# design.net
KiCad netlist of a schematic drawn in Altium Designer
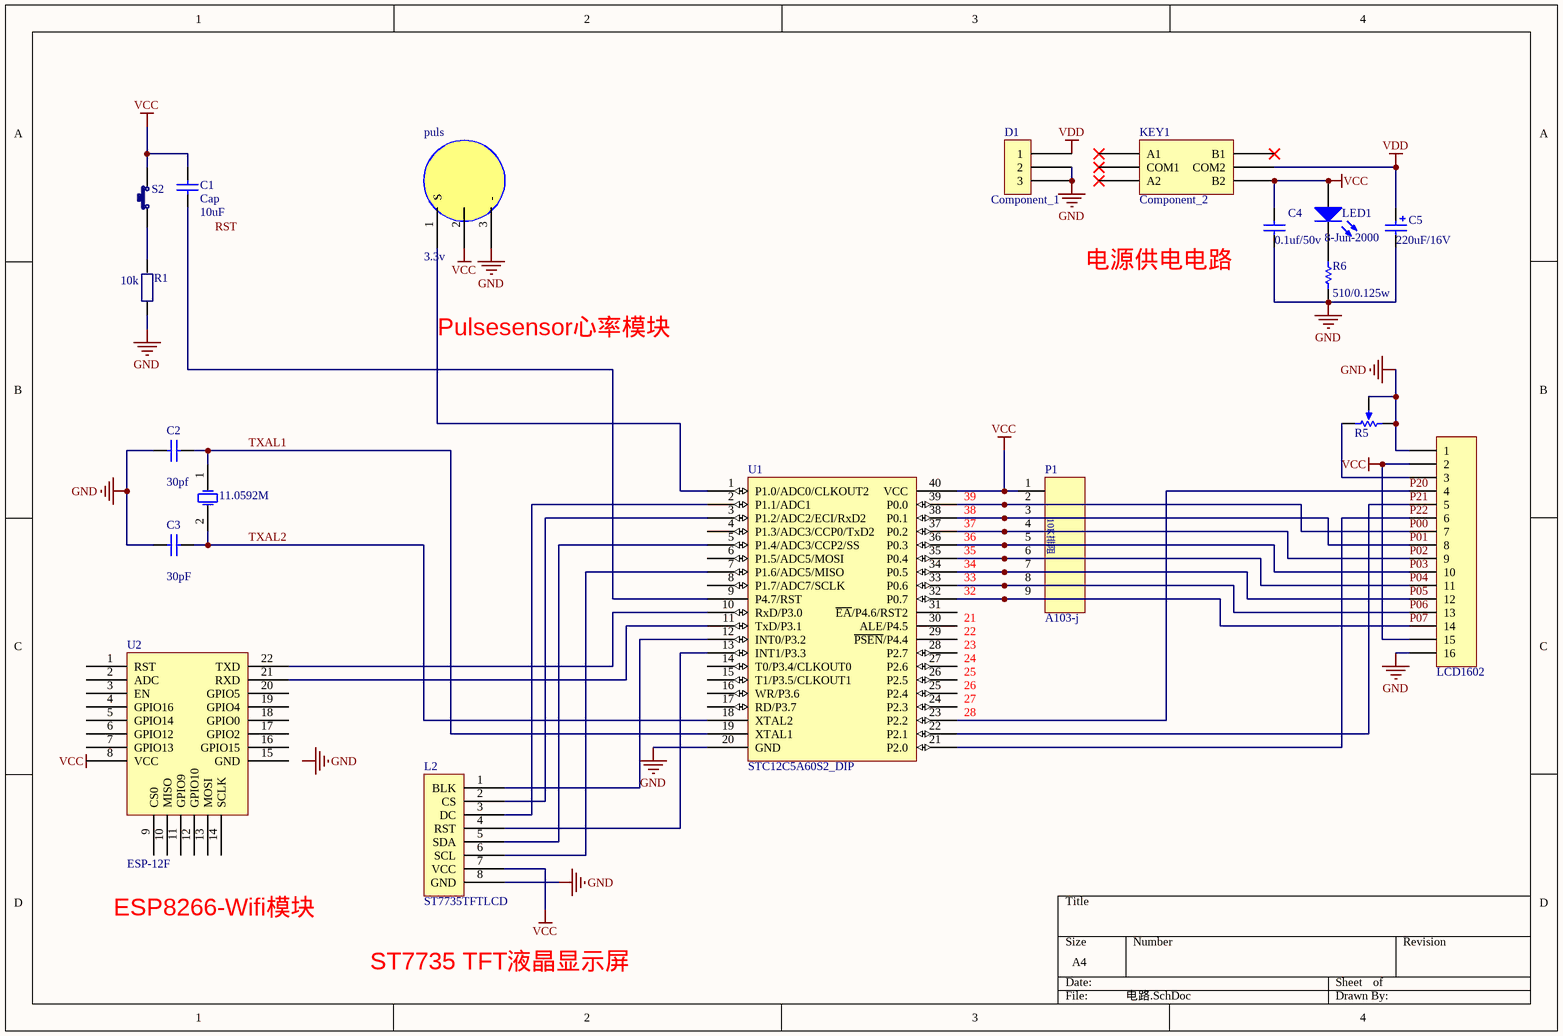
[diagram p0: 电路.SchDoc]

(export (version "E")
  (design (tool "Eeschema 10.0.6"))
  (components
    (comp (ref "11.0592M") (value "晶振") (footprint "XTAL-49/U_N") (libsource (lib "自制库-程文") (part "晶振")))
    (comp (ref "C1")
      (value "Cap")
      (footprint "CAP-0.1")
      (description "Capacitor")
      (fields (field (name "ALTIUM_VALUE") "10uF") (field (name "PUBLISHER") "Altium Limited"))
      (libsource (lib "Miscellaneous Devices") (part "Cap"))
    )
    (comp (ref "C2")
      (value "30pf")
      (footprint "CAP-0.1")
      (description "Capacitor")
      (fields (field (name "PUBLISHER") "Altium Limited"))
      (libsource (lib "Miscellaneous Devices") (part "Cap"))
    )
    (comp (ref "C3")
      (value "30pF")
      (footprint "CAP-0.1")
      (description "Capacitor")
      (fields (field (name "PUBLISHER") "Altium Limited"))
      (libsource (lib "Miscellaneous Devices") (part "Cap"))
    )
    (comp (ref "C4")
      (value "0.1uf/50v")
      (footprint "CAP-0.1")
      (description "Capacitor")
      (fields (field (name "Comment") "Cap") (field (name "PUBLISHER") "Altium Limited"))
      (libsource (lib "Miscellaneous Devices") (part "Cap"))
    )
    (comp (ref "C5")
      (value "220uF/16V")
      (footprint "Capacitor-Disk-Middle")
      (description "Polarized Capacitor (Axial)")
      (fields (field (name "Comment") "Cap Pol2") (field (name "PUBLISHER") "Altium Limited"))
      (libsource (lib "Miscellaneous Devices") (part "Cap Pol2"))
    )
    (comp (ref "D1")
      (value "Component_1")
      (footprint "接插件_DC端口")
      (libsource (lib "DC电源") (part "Component_1"))
    )
    (comp (ref "KEY1")
      (value "Component_2")
      (footprint "sw_8.5mm")
      (libsource (lib "电源开关") (part "Component_1"))
    )
    (comp (ref "L1")
      (value "LCD1602")
      (footprint "HDR1X16")
      (description "Header, 16-Pin")
      (fields (field (name "PUBLISHER") "Altium Limited"))
      (libsource (lib "Miscellaneous Connectors") (part "Header 16"))
    )
    (comp (ref "L2")
      (value "ST7735TFTLCD")
      (footprint "HDR1X8")
      (libsource (lib "Schlib1") (part "ST7735TFTLCD"))
    )
    (comp (ref "LED1")
      (value "LED Chip")
      (footprint "CLED1005-0402")
      (description "Typical Chip LED")
      (fields (field (name "PUBLISHER") "Altium Limited"))
      (libsource (lib "03-EButterflyIntegratedLibrary") (part "LED Chip"))
    )
    (comp (ref "P1") (value "A103-j") (footprint "HDR1X9") (libsource (lib "Schlib1") (part "A103-j")))
    (comp (ref "puls") (value "3.3v") (footprint "HDR1X3") (libsource (lib "Schlib1") (part "puls")))
    (comp (ref "R1")
      (value "10k")
      (footprint "AXIAL-0.5-R")
      (fields (field (name "Comment") "Resistor 贴片"))
      (libsource (lib "自制库-程文") (part "Resistor 贴片"))
    )
    (comp (ref "R5")
      (value "RPot")
      (footprint "VR5")
      (description "Potentiometer")
      (fields (field (name "PUBLISHER") "Altium Limited"))
      (libsource (lib "Miscellaneous Devices") (part "RPot"))
    )
    (comp (ref "R6")
      (value "510/0.125w")
      (footprint "AXIAL-0.3")
      (description "Resistor")
      (fields
        (field (name "PUBLISHED") "8-Jun-2000")
        (field (name "Comment") "Res1")
        (field (name "PUBLISHER") "Altium Limited")
      )
      (libsource (lib "Miscellaneous Devices") (part "Res1"))
    )
    (comp (ref "S2") (value "弹性小按键") (footprint "BUTTON_6*6") (libsource (lib "自制库-程文") (part "弹性小按键")))
    (comp (ref "U1")
      (value "STC12C5A60S2_DIP")
      (footprint "dip40 - 紧缩座")
      (libsource (lib "02 Miscellaneous_Devices_ZSF_Library") (part "STC12C5A60S2_DIP"))
    )
    (comp (ref "U2")
      (value "ESP-12F")
      (footprint "ESP-12F")
      (description "wifi芯片，ESP8266串口WIFI")
      (libsource (lib "02 Miscellaneous_Devices_ZSF_Library") (part "ESP-12F"))
    )
  )
  (nets
    (net (code "8") (name "/28") (class "Default")
      (node (ref "L1") (pin "4") (pinfunction "4_4") (pintype "passive"))
      (node (ref "U1") (pin "23") (pinfunction "P2.2_23") (pintype "bidirectional"))
    )
    (net (code "9") (name "/32") (class "Default")
      (node (ref "L1") (pin "14") (pinfunction "14_14") (pintype "passive"))
      (node (ref "P1") (pin "9") (pinfunction "9_9") (pintype "passive"))
      (node (ref "U1") (pin "32") (pinfunction "P0.7_32") (pintype "bidirectional"))
    )
    (net (code "10") (name "/33") (class "Default")
      (node (ref "L1") (pin "13") (pinfunction "13_13") (pintype "passive"))
      (node (ref "P1") (pin "8") (pinfunction "8_8") (pintype "passive"))
      (node (ref "U1") (pin "33") (pinfunction "P0.6_33") (pintype "bidirectional"))
    )
    (net (code "11") (name "/34") (class "Default")
      (node (ref "L1") (pin "12") (pinfunction "12_12") (pintype "passive"))
      (node (ref "P1") (pin "7") (pinfunction "7_7") (pintype "passive"))
      (node (ref "U1") (pin "34") (pinfunction "P0.5_34") (pintype "bidirectional"))
    )
    (net (code "12") (name "/35") (class "Default")
      (node (ref "L1") (pin "11") (pinfunction "11_11") (pintype "passive"))
      (node (ref "P1") (pin "6") (pinfunction "6_6") (pintype "passive"))
      (node (ref "U1") (pin "35") (pinfunction "P0.4_35") (pintype "bidirectional"))
    )
    (net (code "13") (name "/36") (class "Default")
      (node (ref "L1") (pin "10") (pinfunction "10_10") (pintype "passive"))
      (node (ref "P1") (pin "5") (pinfunction "5_5") (pintype "passive"))
      (node (ref "U1") (pin "36") (pinfunction "P0.3_36") (pintype "bidirectional"))
    )
    (net (code "14") (name "/37") (class "Default")
      (node (ref "L1") (pin "9") (pinfunction "9_9") (pintype "passive"))
      (node (ref "P1") (pin "4") (pinfunction "4_4") (pintype "passive"))
      (node (ref "U1") (pin "37") (pinfunction "P0.2_37") (pintype "bidirectional"))
    )
    (net (code "15") (name "/38") (class "Default")
      (node (ref "L1") (pin "8") (pinfunction "8_8") (pintype "passive"))
      (node (ref "P1") (pin "3") (pinfunction "3_3") (pintype "passive"))
      (node (ref "U1") (pin "38") (pinfunction "P0.1_38") (pintype "bidirectional"))
    )
    (net (code "16") (name "/39") (class "Default")
      (node (ref "L1") (pin "7") (pinfunction "7_7") (pintype "passive"))
      (node (ref "P1") (pin "2") (pinfunction "2_2") (pintype "passive"))
      (node (ref "U1") (pin "39") (pinfunction "P0.0_39") (pintype "bidirectional"))
    )
    (net (code "17") (name "/P21") (class "Default")
      (node (ref "L1") (pin "5") (pinfunction "5_5") (pintype "passive"))
      (node (ref "U1") (pin "22") (pinfunction "P2.1_22") (pintype "bidirectional"))
    )
    (net (code "18") (name "/P22") (class "Default")
      (node (ref "L1") (pin "6") (pinfunction "6_6") (pintype "passive"))
      (node (ref "U1") (pin "21") (pinfunction "P2.0_21") (pintype "bidirectional"))
    )
    (net (code "20") (name "/TXAL1") (class "Default")
      (node (ref "11.0592M") (pin "1") (pinfunction "OSC1_1") (pintype "passive"))
      (node (ref "C2") (pin "2") (pinfunction "2_2") (pintype "passive"))
      (node (ref "U1") (pin "19") (pinfunction "XTAL1_19") (pintype "passive"))
    )
    (net (code "21") (name "/TXAL2") (class "Default")
      (node (ref "11.0592M") (pin "2") (pinfunction "OSC2_2") (pintype "passive"))
      (node (ref "C3") (pin "2") (pinfunction "2_2") (pintype "passive"))
      (node (ref "U1") (pin "18") (pinfunction "XTAL2_18") (pintype "passive"))
    )
    (net (code "22") (name "GND") (class "Default")
      (node (ref "C2") (pin "1") (pinfunction "1_1") (pintype "passive"))
      (node (ref "C3") (pin "1") (pinfunction "1_1") (pintype "passive"))
      (node (ref "C4") (pin "1") (pinfunction "1_1") (pintype "passive"))
      (node (ref "C5") (pin "2") (pinfunction "2_2") (pintype "passive"))
      (node (ref "D1") (pin "2") (pinfunction "2_2") (pintype "passive"))
      (node (ref "D1") (pin "3") (pinfunction "3_3") (pintype "passive"))
      (node (ref "L1") (pin "1") (pinfunction "1_1") (pintype "passive"))
      (node (ref "L1") (pin "16") (pinfunction "16_16") (pintype "passive"))
      (node (ref "L2") (pin "8") (pinfunction "GND_8") (pintype "passive"))
      (node (ref "R1") (pin "1") (pintype "passive"))
      (node (ref "R5") (pin "1") (pinfunction "TOP_1") (pintype "passive"))
      (node (ref "R5") (pin "2") (pinfunction "TAP_2") (pintype "passive"))
      (node (ref "R6") (pin "1") (pinfunction "1_1") (pintype "passive"))
      (node (ref "U1") (pin "20") (pinfunction "GND_20") (pintype "power_in"))
      (node (ref "puls") (pin "3") (pinfunction "-_3") (pintype "passive"))
    )
    (net (code "23") (name "Net-(L2-BLK)") (class "Default")
      (node (ref "L2") (pin "1") (pinfunction "BLK_1") (pintype "passive"))
      (node (ref "U1") (pin "12") (pinfunction "INT0/P3.2_12") (pintype "bidirectional"))
    )
    (net (code "24") (name "Net-(L2-CS)") (class "Default")
      (node (ref "L2") (pin "2") (pinfunction "CS_2") (pintype "passive"))
      (node (ref "U1") (pin "3") (pinfunction "P1.2/ADC2/ECI/RxD2_3") (pintype "bidirectional"))
    )
    (net (code "25") (name "Net-(L2-DC)") (class "Default")
      (node (ref "L2") (pin "3") (pinfunction "DC_3") (pintype "passive"))
      (node (ref "U1") (pin "2") (pinfunction "P1.1/ADC1_2") (pintype "bidirectional"))
    )
    (net (code "26") (name "Net-(L2-RST)") (class "Default")
      (node (ref "L2") (pin "4") (pinfunction "RST_4") (pintype "passive"))
      (node (ref "U1") (pin "13") (pinfunction "INT1/P3.3_13") (pintype "bidirectional"))
    )
    (net (code "27") (name "Net-(L2-SCL)") (class "Default")
      (node (ref "L2") (pin "6") (pinfunction "SCL_6") (pintype "passive"))
      (node (ref "U1") (pin "7") (pinfunction "P1.6/ADC5/MISO_7") (pintype "bidirectional"))
    )
    (net (code "28") (name "Net-(L2-SDA)") (class "Default")
      (node (ref "L2") (pin "5") (pinfunction "SDA_5") (pintype "passive"))
      (node (ref "U1") (pin "5") (pinfunction "P1.4/ADC3/CCP2/SS_5") (pintype "bidirectional"))
    )
    (net (code "29") (name "Net-(LED1-K)") (class "Default")
      (node (ref "LED1") (pin "2") (pinfunction "K_2") (pintype "passive"))
      (node (ref "R6") (pin "2") (pinfunction "2_2") (pintype "passive"))
    )
    (net (code "30") (name "Net-(R5-BOT)") (class "Default")
      (node (ref "L1") (pin "3") (pinfunction "3_3") (pintype "passive"))
      (node (ref "R5") (pin "3") (pinfunction "BOT_3") (pintype "passive"))
    )
    (net (code "31") (name "Net-(S2-0)") (class "Default")
      (node (ref "R1") (pin "2") (pintype "passive"))
      (node (ref "S2") (pin "1") (pinfunction "0_1") (pintype "passive"))
    )
    (net (code "32") (name "Net-(U1-P1.0{slash}ADC0{slash}CLKOUT2)") (class "Default")
      (node (ref "U1") (pin "1") (pinfunction "P1.0/ADC0/CLKOUT2_1") (pintype "bidirectional"))
      (node (ref "puls") (pin "1") (pinfunction "S_1") (pintype "passive"))
    )
    (net (code "33") (name "Net-(U1-P4.7{slash}RST)") (class "Default")
      (node (ref "C1") (pin "1") (pinfunction "1_1") (pintype "passive"))
      (node (ref "U1") (pin "9") (pinfunction "P4.7/RST_9") (pintype "passive"))
    )
    (net (code "34") (name "Net-(U1-RxD{slash}P3.0)") (class "Default")
      (node (ref "U1") (pin "10") (pinfunction "RxD/P3.0_10") (pintype "bidirectional"))
      (node (ref "U2") (pin "22") (pinfunction "TXD_22") (pintype "passive"))
    )
    (net (code "35") (name "Net-(U1-TxD{slash}P3.1)") (class "Default")
      (node (ref "U1") (pin "11") (pinfunction "TxD/P3.1_11") (pintype "bidirectional"))
      (node (ref "U2") (pin "21") (pinfunction "RXD_21") (pintype "passive"))
    )
    (net (code "36") (name "VCC") (class "Default")
      (node (ref "C1") (pin "2") (pinfunction "2_2") (pintype "passive"))
      (node (ref "C4") (pin "2") (pinfunction "2_2") (pintype "passive"))
      (node (ref "KEY1") (pin "6") (pinfunction "B2_6") (pintype "passive"))
      (node (ref "L1") (pin "15") (pinfunction "15_15") (pintype "passive"))
      (node (ref "L1") (pin "2") (pinfunction "2_2") (pintype "passive"))
      (node (ref "L2") (pin "7") (pinfunction "VCC_7") (pintype "passive"))
      (node (ref "LED1") (pin "1") (pinfunction "A_1") (pintype "passive"))
      (node (ref "P1") (pin "1") (pinfunction "1_1") (pintype "passive"))
      (node (ref "S2") (pin "2") (pinfunction "1_2") (pintype "passive"))
      (node (ref "U1") (pin "40") (pinfunction "VCC_40") (pintype "power_in"))
      (node (ref "puls") (pin "2") (pintype "passive"))
    )
    (net (code "37") (name "VDD") (class "Default")
      (node (ref "C5") (pin "1") (pinfunction "1_1") (pintype "passive"))
      (node (ref "D1") (pin "1") (pinfunction "1_1") (pintype "passive"))
      (node (ref "KEY1") (pin "5") (pinfunction "COM2_5") (pintype "passive"))
    )
    (net (code "38") (name "unconnected-(KEY1-A1-Pad1)") (class "Default")
      (node (ref "KEY1") (pin "1") (pinfunction "A1_1") (pintype "passive+no_connect"))
    )
    (net (code "39") (name "unconnected-(KEY1-A2-Pad3)") (class "Default")
      (node (ref "KEY1") (pin "3") (pinfunction "A2_3") (pintype "passive+no_connect"))
    )
    (net (code "40") (name "unconnected-(KEY1-B1-Pad4)") (class "Default")
      (node (ref "KEY1") (pin "4") (pinfunction "B1_4") (pintype "passive+no_connect"))
    )
    (net (code "41") (name "unconnected-(KEY1-COM1-Pad2)") (class "Default")
      (node (ref "KEY1") (pin "2") (pinfunction "COM1_2") (pintype "passive+no_connect"))
    )
    (net (code "42") (name "unconnected-(U1-ALE{slash}P4.5-Pad30)") (class "Default")
      (node (ref "U1") (pin "30") (pinfunction "ALE/P4.5_30") (pintype "passive"))
    )
    (net (code "43") (name "unconnected-(U1-P1.3{slash}ADC3{slash}CCP0{slash}TxD2-Pad4)") (class "Default")
      (node (ref "U1") (pin "4") (pinfunction "P1.3/ADC3/CCP0/TxD2_4") (pintype "bidirectional"))
    )
    (net (code "44") (name "unconnected-(U1-P1.5{slash}ADC5{slash}MOSI-Pad6)") (class "Default")
      (node (ref "U1") (pin "6") (pinfunction "P1.5/ADC5/MOSI_6") (pintype "bidirectional"))
    )
    (net (code "45") (name "unconnected-(U1-P1.7{slash}ADC7{slash}SCLK-Pad8)") (class "Default")
      (node (ref "U1") (pin "8") (pinfunction "P1.7/ADC7/SCLK_8") (pintype "bidirectional"))
    )
    (net (code "46") (name "unconnected-(U1-P2.3-Pad24)") (class "Default")
      (node (ref "U1") (pin "24") (pinfunction "P2.3_24") (pintype "bidirectional"))
    )
    (net (code "47") (name "unconnected-(U1-P2.4-Pad25)") (class "Default")
      (node (ref "U1") (pin "25") (pinfunction "P2.4_25") (pintype "bidirectional"))
    )
    (net (code "48") (name "unconnected-(U1-P2.5-Pad26)") (class "Default")
      (node (ref "U1") (pin "26") (pinfunction "P2.5_26") (pintype "bidirectional"))
    )
    (net (code "49") (name "unconnected-(U1-P2.6-Pad27)") (class "Default")
      (node (ref "U1") (pin "27") (pinfunction "P2.6_27") (pintype "bidirectional"))
    )
    (net (code "50") (name "unconnected-(U1-P2.7-Pad28)") (class "Default")
      (node (ref "U1") (pin "28") (pinfunction "P2.7_28") (pintype "bidirectional"))
    )
    (net (code "51") (name "unconnected-(U1-RD{slash}P3.7-Pad17)") (class "Default")
      (node (ref "U1") (pin "17") (pinfunction "RD/P3.7_17") (pintype "bidirectional"))
    )
    (net (code "52") (name "unconnected-(U1-T0{slash}P3.4{slash}CLKOUT0-Pad14)") (class "Default")
      (node (ref "U1") (pin "14") (pinfunction "T0/P3.4/CLKOUT0_14") (pintype "bidirectional"))
    )
    (net (code "53") (name "unconnected-(U1-T1{slash}P3.5{slash}CLKOUT1-Pad15)") (class "Default")
      (node (ref "U1") (pin "15") (pinfunction "T1/P3.5/CLKOUT1_15") (pintype "bidirectional"))
    )
    (net (code "54") (name "unconnected-(U1-WR{slash}P3.6-Pad16)") (class "Default")
      (node (ref "U1") (pin "16") (pinfunction "WR/P3.6_16") (pintype "bidirectional"))
    )
    (net (code "55") (name "unconnected-(U1-~{EA}{slash}P4.6{slash}RST2-Pad31)") (class "Default")
      (node (ref "U1") (pin "31") (pinfunction "~{EA}/P4.6/RST2_31") (pintype "passive"))
    )
    (net (code "56") (name "unconnected-(U1-~{PSEN}{slash}P4.4-Pad29)") (class "Default")
      (node (ref "U1") (pin "29") (pinfunction "~{PSEN}/P4.4_29") (pintype "passive"))
    )
    (net (code "57") (name "unconnected-(U2-ADC-Pad2)") (class "Default")
      (node (ref "U2") (pin "2") (pinfunction "ADC_2") (pintype "passive"))
    )
    (net (code "58") (name "unconnected-(U2-CS0-Pad9)") (class "Default")
      (node (ref "U2") (pin "9") (pinfunction "CS0_9") (pintype "passive"))
    )
    (net (code "59") (name "unconnected-(U2-EN-Pad3)") (class "Default")
      (node (ref "U2") (pin "3") (pinfunction "EN_3") (pintype "passive"))
    )
    (net (code "60") (name "unconnected-(U2-GND-Pad15)") (class "Default")
      (node (ref "U2") (pin "15") (pinfunction "GND_15") (pintype "passive"))
    )
    (net (code "61") (name "unconnected-(U2-GPIO0-Pad18)") (class "Default")
      (node (ref "U2") (pin "18") (pinfunction "GPIO0_18") (pintype "passive"))
    )
    (net (code "62") (name "unconnected-(U2-GPIO2-Pad17)") (class "Default")
      (node (ref "U2") (pin "17") (pinfunction "GPIO2_17") (pintype "passive"))
    )
    (net (code "63") (name "unconnected-(U2-GPIO4-Pad19)") (class "Default")
      (node (ref "U2") (pin "19") (pinfunction "GPIO4_19") (pintype "passive"))
    )
    (net (code "64") (name "unconnected-(U2-GPIO5-Pad20)") (class "Default")
      (node (ref "U2") (pin "20") (pinfunction "GPIO5_20") (pintype "passive"))
    )
    (net (code "65") (name "unconnected-(U2-GPIO9-Pad11)") (class "Default")
      (node (ref "U2") (pin "11") (pinfunction "GPIO9_11") (pintype "passive"))
    )
    (net (code "66") (name "unconnected-(U2-GPIO10-Pad12)") (class "Default")
      (node (ref "U2") (pin "12") (pinfunction "GPIO10_12") (pintype "passive"))
    )
    (net (code "67") (name "unconnected-(U2-GPIO12-Pad6)") (class "Default")
      (node (ref "U2") (pin "6") (pinfunction "GPIO12_6") (pintype "passive"))
    )
    (net (code "68") (name "unconnected-(U2-GPIO13-Pad7)") (class "Default")
      (node (ref "U2") (pin "7") (pinfunction "GPIO13_7") (pintype "passive"))
    )
    (net (code "69") (name "unconnected-(U2-GPIO14-Pad5)") (class "Default")
      (node (ref "U2") (pin "5") (pinfunction "GPIO14_5") (pintype "passive"))
    )
    (net (code "70") (name "unconnected-(U2-GPIO15-Pad16)") (class "Default")
      (node (ref "U2") (pin "16") (pinfunction "GPIO15_16") (pintype "passive"))
    )
    (net (code "71") (name "unconnected-(U2-GPIO16-Pad4)") (class "Default")
      (node (ref "U2") (pin "4") (pinfunction "GPIO16_4") (pintype "passive"))
    )
    (net (code "72") (name "unconnected-(U2-MISO-Pad10)") (class "Default")
      (node (ref "U2") (pin "10") (pinfunction "MISO_10") (pintype "passive"))
    )
    (net (code "73") (name "unconnected-(U2-MOSI-Pad13)") (class "Default")
      (node (ref "U2") (pin "13") (pinfunction "MOSI_13") (pintype "passive"))
    )
    (net (code "74") (name "unconnected-(U2-RST-Pad1)") (class "Default")
      (node (ref "U2") (pin "1") (pinfunction "RST_1") (pintype "passive"))
    )
    (net (code "75") (name "unconnected-(U2-SCLK-Pad14)") (class "Default")
      (node (ref "U2") (pin "14") (pinfunction "SCLK_14") (pintype "passive"))
    )
    (net (code "76") (name "unconnected-(U2-VCC-Pad8)") (class "Default")
      (node (ref "U2") (pin "8") (pinfunction "VCC_8") (pintype "passive"))
    )
  )
)
